# Adafruit_EZ-SFX_Mini.net
KiCad netlist of a schematic drawn in EAGLE
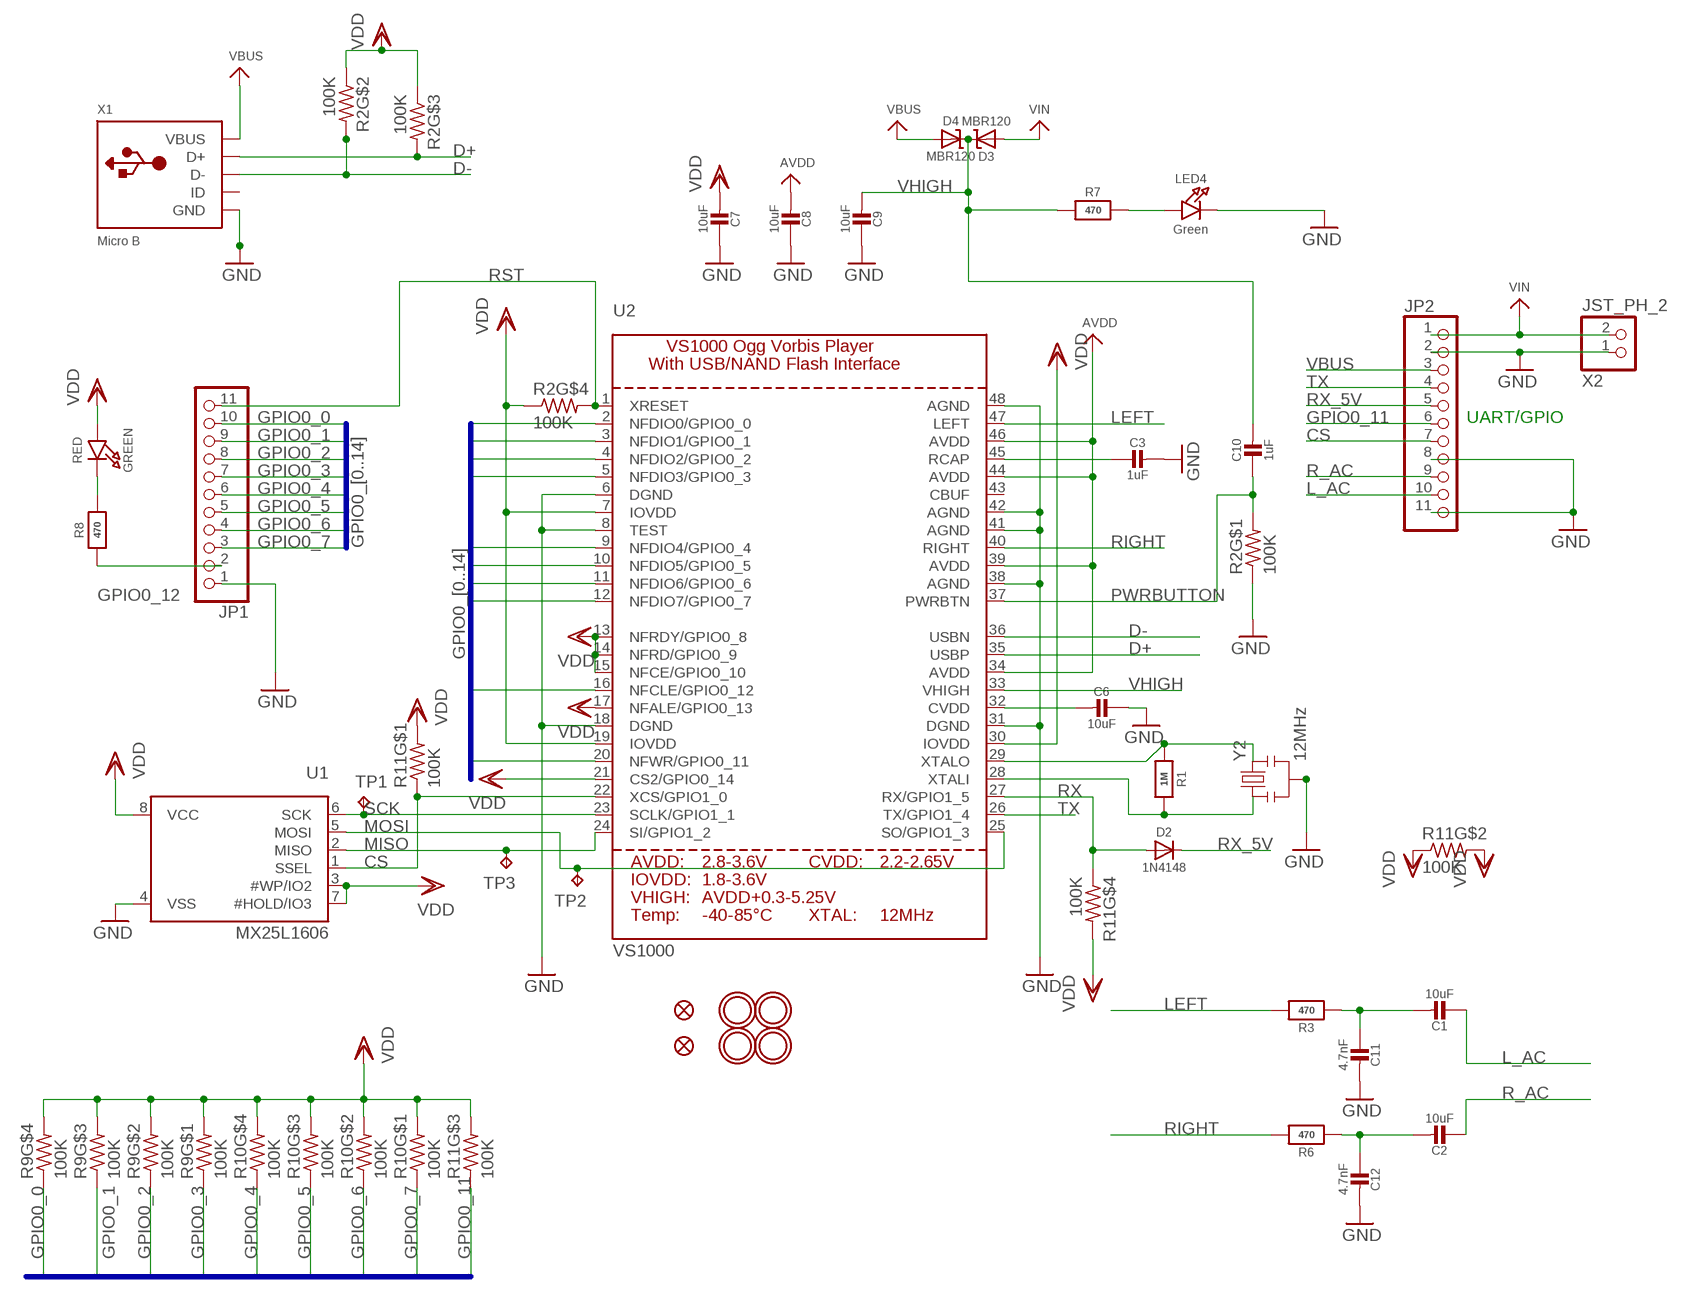
[diagram p0: schematic, sheet 1]

(export (version "E")
  (design (tool "Eeschema 10.0.6"))
  (components
    (comp (ref "C1")
      (value "10uF")
      (footprint "eagle-import:0805-NO")
      (libsource (lib "eagle-import") (part "CAP_CERAMIC0805-NOOUTLINE"))
    )
    (comp (ref "C2")
      (value "10uF")
      (footprint "eagle-import:0805-NO")
      (libsource (lib "eagle-import") (part "CAP_CERAMIC0805-NOOUTLINE"))
    )
    (comp (ref "C3")
      (value "1uF")
      (footprint "eagle-import:0805-NO")
      (libsource (lib "eagle-import") (part "CAP_CERAMIC0805-NOOUTLINE"))
    )
    (comp (ref "C6")
      (value "10uF")
      (footprint "eagle-import:0805_10MGAP")
      (libsource (lib "eagle-import") (part "CAP_CERAMIC0805_10MGAP"))
    )
    (comp (ref "C7")
      (value "10uF")
      (footprint "eagle-import:0805_10MGAP")
      (libsource (lib "eagle-import") (part "CAP_CERAMIC0805_10MGAP"))
    )
    (comp (ref "C8")
      (value "10uF")
      (footprint "eagle-import:0805-NO")
      (libsource (lib "eagle-import") (part "CAP_CERAMIC0805-NOOUTLINE"))
    )
    (comp (ref "C9")
      (value "10uF")
      (footprint "eagle-import:0805-NO")
      (libsource (lib "eagle-import") (part "CAP_CERAMIC0805-NOOUTLINE"))
    )
    (comp (ref "C10")
      (value "1uF")
      (footprint "eagle-import:0805-NO")
      (libsource (lib "eagle-import") (part "CAP_CERAMIC0805-NOOUTLINE"))
    )
    (comp (ref "C11")
      (value "4.7nF")
      (footprint "eagle-import:0805-NO")
      (libsource (lib "eagle-import") (part "CAP_CERAMIC0805-NOOUTLINE"))
    )
    (comp (ref "C12")
      (value "4.7nF")
      (footprint "eagle-import:0805-NO")
      (libsource (lib "eagle-import") (part "CAP_CERAMIC0805-NOOUTLINE"))
    )
    (comp (ref "D2")
      (value "1N4148")
      (footprint "eagle-import:SOD-323")
      (libsource (lib "eagle-import") (part "DIODESOD-323"))
    )
    (comp (ref "D3")
      (value "MBR120")
      (footprint "eagle-import:SOD-123")
      (libsource (lib "eagle-import") (part "DIODE-SCHOTTKYSOD-123"))
    )
    (comp (ref "D4")
      (value "MBR120")
      (footprint "eagle-import:SOD-123")
      (libsource (lib "eagle-import") (part "DIODE-SCHOTTKYSOD-123"))
    )
    (comp (ref "FID1")
      (value "FIDUCIAL\"\"")
      (footprint "eagle-import:FIDUCIAL_1MM")
      (libsource (lib "eagle-import") (part "FIDUCIAL{dblquote}{dblquote}"))
    )
    (comp (ref "FID2")
      (value "FIDUCIAL\"\"")
      (footprint "eagle-import:FIDUCIAL_1MM")
      (libsource (lib "eagle-import") (part "FIDUCIAL{dblquote}{dblquote}"))
    )
    (comp (ref "GREEN")
      (value "RED")
      (footprint "eagle-import:CHIPLED_0805_NOOUTLINE")
      (libsource (lib "eagle-import") (part "LED0805_NOOUTLINE"))
    )
    (comp (ref "JP1")
      (value "HEADER-1X1176MIL")
      (footprint "eagle-import:1X11_ROUND_76")
      (libsource (lib "eagle-import") (part "HEADER-1X1176MIL"))
    )
    (comp (ref "JP2")
      (value "HEADER-1X1176MIL")
      (footprint "eagle-import:1X11_ROUND_76")
      (libsource (lib "eagle-import") (part "HEADER-1X1176MIL"))
    )
    (comp (ref "LED4")
      (value "Green")
      (footprint "eagle-import:CHIPLED_0805_NOOUTLINE")
      (libsource (lib "eagle-import") (part "LED0805_NOOUTLINE"))
    )
    (comp (ref "R1")
      (value "1M")
      (footprint "eagle-import:_0805MP")
      (libsource (lib "eagle-import") (part "RESISTOR_0805MP"))
    )
    (comp (ref "R2")
      (value "100K")
      (footprint "eagle-import:RESPACK_4X0603")
      (libsource (lib "eagle-import") (part "RESISTOR_4PACK_US"))
    )
    (comp (ref "R3")
      (value "470")
      (footprint "eagle-import:0805-NO")
      (libsource (lib "eagle-import") (part "RESISTOR0805_NOOUTLINE"))
    )
    (comp (ref "R6")
      (value "470")
      (footprint "eagle-import:0805-NO")
      (libsource (lib "eagle-import") (part "RESISTOR0805_NOOUTLINE"))
    )
    (comp (ref "R7")
      (value "470")
      (footprint "eagle-import:0805-NO")
      (libsource (lib "eagle-import") (part "RESISTOR0805_NOOUTLINE"))
    )
    (comp (ref "R8")
      (value "470")
      (footprint "eagle-import:0805-NO")
      (libsource (lib "eagle-import") (part "RESISTOR0805_NOOUTLINE"))
    )
    (comp (ref "R9")
      (value "100K")
      (footprint "eagle-import:RESPACK_4X0603")
      (libsource (lib "eagle-import") (part "RESISTOR_4PACK_US"))
    )
    (comp (ref "R10")
      (value "100K")
      (footprint "eagle-import:RESPACK_4X0603")
      (libsource (lib "eagle-import") (part "RESISTOR_4PACK_US"))
    )
    (comp (ref "R11")
      (value "100K")
      (footprint "eagle-import:RESPACK_4X0603")
      (libsource (lib "eagle-import") (part "RESISTOR_4PACK_US"))
    )
    (comp (ref "TP1")
      (value "TPB1,27")
      (footprint "eagle-import:B1,27")
      (libsource (lib "eagle-import") (part "TPB1,27"))
    )
    (comp (ref "TP2")
      (value "TPB1,27")
      (footprint "eagle-import:B1,27")
      (libsource (lib "eagle-import") (part "TPB1,27"))
    )
    (comp (ref "TP3")
      (value "TPB1,27")
      (footprint "eagle-import:B1,27")
      (libsource (lib "eagle-import") (part "TPB1,27"))
    )
    (comp (ref "U$5")
      (value "MOUNTINGHOLE2.5")
      (footprint "eagle-import:MOUNTINGHOLE_2.5_PLATED")
      (libsource (lib "eagle-import") (part "MOUNTINGHOLE2.5"))
    )
    (comp (ref "U$6")
      (value "MOUNTINGHOLE2.5")
      (footprint "eagle-import:MOUNTINGHOLE_2.5_PLATED")
      (libsource (lib "eagle-import") (part "MOUNTINGHOLE2.5"))
    )
    (comp (ref "U$7")
      (value "MOUNTINGHOLE2.5")
      (footprint "eagle-import:MOUNTINGHOLE_2.5_PLATED")
      (libsource (lib "eagle-import") (part "MOUNTINGHOLE2.5"))
    )
    (comp (ref "U$8")
      (value "MOUNTINGHOLE2.5")
      (footprint "eagle-import:MOUNTINGHOLE_2.5_PLATED")
      (libsource (lib "eagle-import") (part "MOUNTINGHOLE2.5"))
    )
    (comp (ref "U1")
      (value "MX25L1606")
      (footprint "eagle-import:SOIC8_208MIL")
      (libsource (lib "eagle-import") (part "SPIFLASH_SOIC8208MIL"))
    )
    (comp (ref "U2")
      (value "VS1000")
      (footprint "eagle-import:LQFP48")
      (libsource (lib "eagle-import") (part "VS1000"))
    )
    (comp (ref "X1")
      (value "Micro B")
      (footprint "eagle-import:4UCONN_20329_V2")
      (libsource (lib "eagle-import") (part "USB_MICRO_20329_V2"))
    )
    (comp (ref "X2")
      (value "JST_PH_2")
      (footprint "eagle-import:JSTPH2")
      (libsource (lib "eagle-import") (part "CON_JST_PH_2PIN"))
    )
    (comp (ref "Y2")
      (value "12MHz")
      (footprint "eagle-import:RESONATOR-SMD")
      (libsource (lib "eagle-import") (part "RESONATORSMD"))
    )
  )
  (nets
    (net (code "6") (name "/CS") (class "Default")
      (node (ref "JP2") (pin "7") (pinfunction "7_7") (pintype "passive"))
      (node (ref "R11") (pin "1") (pinfunction "1_1") (pintype "passive"))
      (node (ref "U1") (pin "1") (pinfunction "SSEL_1") (pintype "bidirectional"))
      (node (ref "U2") (pin "22") (pinfunction "XCS/GPIO1_0_22") (pintype "bidirectional"))
    )
    (net (code "7") (name "/D+") (class "Default")
      (node (ref "R2") (pin "6") (pinfunction "2_6") (pintype "passive"))
      (node (ref "U2") (pin "35") (pinfunction "USBP_35") (pintype "bidirectional"))
      (node (ref "X1") (pin "D+") (pinfunction "D+_D+") (pintype "bidirectional"))
    )
    (net (code "8") (name "/D-") (class "Default")
      (node (ref "R2") (pin "7") (pinfunction "2_7") (pintype "passive"))
      (node (ref "U2") (pin "36") (pinfunction "USBN_36") (pintype "bidirectional"))
      (node (ref "X1") (pin "D-") (pinfunction "D-_D-") (pintype "bidirectional"))
    )
    (net (code "9") (name "/GPIO0_0") (class "Default")
      (node (ref "JP1") (pin "10") (pinfunction "10_10") (pintype "passive"))
      (node (ref "R9") (pin "4") (pinfunction "1_4") (pintype "passive"))
      (node (ref "U2") (pin "2") (pinfunction "NFDIO0/GPIO0_0_2") (pintype "bidirectional"))
    )
    (net (code "10") (name "/GPIO0_1") (class "Default")
      (node (ref "JP1") (pin "9") (pinfunction "9_9") (pintype "passive"))
      (node (ref "R9") (pin "3") (pinfunction "1_3") (pintype "passive"))
      (node (ref "U2") (pin "3") (pinfunction "NFDIO1/GPIO0_1_3") (pintype "bidirectional"))
    )
    (net (code "11") (name "/GPIO0_2") (class "Default")
      (node (ref "JP1") (pin "8") (pinfunction "8_8") (pintype "passive"))
      (node (ref "R9") (pin "2") (pinfunction "1_2") (pintype "passive"))
      (node (ref "U2") (pin "4") (pinfunction "NFDIO2/GPIO0_2_4") (pintype "bidirectional"))
    )
    (net (code "12") (name "/GPIO0_3") (class "Default")
      (node (ref "JP1") (pin "7") (pinfunction "7_7") (pintype "passive"))
      (node (ref "R9") (pin "1") (pinfunction "1_1") (pintype "passive"))
      (node (ref "U2") (pin "5") (pinfunction "NFDIO3/GPIO0_3_5") (pintype "bidirectional"))
    )
    (net (code "13") (name "/GPIO0_4") (class "Default")
      (node (ref "JP1") (pin "6") (pinfunction "6_6") (pintype "passive"))
      (node (ref "R10") (pin "4") (pinfunction "1_4") (pintype "passive"))
      (node (ref "U2") (pin "9") (pinfunction "NFDIO4/GPIO0_4_9") (pintype "bidirectional"))
    )
    (net (code "14") (name "/GPIO0_5") (class "Default")
      (node (ref "JP1") (pin "5") (pinfunction "5_5") (pintype "passive"))
      (node (ref "R10") (pin "3") (pinfunction "1_3") (pintype "passive"))
      (node (ref "U2") (pin "10") (pinfunction "NFDIO5/GPIO0_5_10") (pintype "bidirectional"))
    )
    (net (code "15") (name "/GPIO0_6") (class "Default")
      (node (ref "JP1") (pin "4") (pinfunction "4_4") (pintype "passive"))
      (node (ref "R10") (pin "2") (pinfunction "1_2") (pintype "passive"))
      (node (ref "U2") (pin "11") (pinfunction "NFDIO6/GPIO0_6_11") (pintype "bidirectional"))
    )
    (net (code "16") (name "/GPIO0_7") (class "Default")
      (node (ref "JP1") (pin "3") (pinfunction "3_3") (pintype "passive"))
      (node (ref "R10") (pin "1") (pinfunction "1_1") (pintype "passive"))
      (node (ref "U2") (pin "12") (pinfunction "NFDIO7/GPIO0_7_12") (pintype "bidirectional"))
    )
    (net (code "17") (name "/GPIO0_11") (class "Default")
      (node (ref "JP2") (pin "6") (pinfunction "6_6") (pintype "passive"))
      (node (ref "R11") (pin "3") (pinfunction "1_3") (pintype "passive"))
      (node (ref "U2") (pin "20") (pinfunction "NFWR/GPIO0_11_20") (pintype "bidirectional"))
    )
    (net (code "18") (name "/GPIO0_12") (class "Default")
      (node (ref "JP1") (pin "2") (pinfunction "2_2") (pintype "passive"))
      (node (ref "R8") (pin "2") (pinfunction "2_2") (pintype "passive"))
      (node (ref "U2") (pin "16") (pinfunction "NFCLE/GPIO0_12_16") (pintype "bidirectional"))
    )
    (net (code "20") (name "/LEFT") (class "Default")
      (node (ref "R3") (pin "1") (pinfunction "1_1") (pintype "passive"))
      (node (ref "U2") (pin "47") (pinfunction "LEFT_47") (pintype "bidirectional"))
    )
    (net (code "21") (name "/L_AC") (class "Default")
      (node (ref "C1") (pin "1") (pinfunction "1_1") (pintype "passive"))
      (node (ref "JP2") (pin "10") (pinfunction "10_10") (pintype "passive"))
    )
    (net (code "22") (name "/MISO") (class "Default")
      (node (ref "TP3") (pin "TP") (pinfunction "TP_TP") (pintype "input"))
      (node (ref "U1") (pin "2") (pinfunction "MISO_2") (pintype "bidirectional"))
      (node (ref "U2") (pin "24") (pinfunction "SI/GPIO1_2_24") (pintype "bidirectional"))
    )
    (net (code "23") (name "/MOSI") (class "Default")
      (node (ref "TP2") (pin "TP") (pinfunction "TP_TP") (pintype "input"))
      (node (ref "U1") (pin "5") (pinfunction "MOSI_5") (pintype "bidirectional"))
      (node (ref "U2") (pin "25") (pinfunction "SO/GPIO1_3_25") (pintype "bidirectional"))
    )
    (net (code "24") (name "/PWRBUTTON") (class "Default")
      (node (ref "C10") (pin "1") (pinfunction "1_1") (pintype "passive"))
      (node (ref "R2") (pin "8") (pinfunction "2_8") (pintype "passive"))
      (node (ref "U2") (pin "37") (pinfunction "PWRBTN_37") (pintype "bidirectional"))
    )
    (net (code "25") (name "/RIGHT") (class "Default")
      (node (ref "R6") (pin "1") (pinfunction "1_1") (pintype "passive"))
      (node (ref "U2") (pin "40") (pinfunction "RIGHT_40") (pintype "bidirectional"))
    )
    (net (code "26") (name "/RST") (class "Default")
      (node (ref "JP1") (pin "11") (pinfunction "11_11") (pintype "passive"))
      (node (ref "R2") (pin "5") (pinfunction "2_5") (pintype "passive"))
      (node (ref "U2") (pin "1") (pinfunction "XRESET_1") (pintype "bidirectional"))
    )
    (net (code "27") (name "/RX") (class "Default")
      (node (ref "D2") (pin "A") (pinfunction "A_A") (pintype "passive"))
      (node (ref "R11") (pin "4") (pinfunction "1_4") (pintype "passive"))
      (node (ref "U2") (pin "27") (pinfunction "RX/GPIO1_5_27") (pintype "bidirectional"))
    )
    (net (code "28") (name "/RX_5V") (class "Default")
      (node (ref "D2") (pin "C") (pinfunction "C_C") (pintype "passive"))
      (node (ref "JP2") (pin "5") (pinfunction "5_5") (pintype "passive"))
    )
    (net (code "29") (name "/R_AC") (class "Default")
      (node (ref "C2") (pin "1") (pinfunction "1_1") (pintype "passive"))
      (node (ref "JP2") (pin "9") (pinfunction "9_9") (pintype "passive"))
    )
    (net (code "30") (name "/SCK") (class "Default")
      (node (ref "TP1") (pin "TP") (pinfunction "TP_TP") (pintype "input"))
      (node (ref "U1") (pin "6") (pinfunction "SCK_6") (pintype "bidirectional"))
      (node (ref "U2") (pin "23") (pinfunction "SCLK/GPIO1_1_23") (pintype "bidirectional"))
    )
    (net (code "31") (name "/TX") (class "Default")
      (node (ref "JP2") (pin "4") (pinfunction "4_4") (pintype "passive"))
      (node (ref "U2") (pin "26") (pinfunction "TX/GPIO1_4_26") (pintype "bidirectional"))
    )
    (net (code "32") (name "/VHIGH") (class "Default")
      (node (ref "C10") (pin "2") (pinfunction "2_2") (pintype "passive"))
      (node (ref "C9") (pin "2") (pinfunction "2_2") (pintype "passive"))
      (node (ref "D3") (pin "C") (pinfunction "C_C") (pintype "passive"))
      (node (ref "D4") (pin "C") (pinfunction "C_C") (pintype "passive"))
      (node (ref "R7") (pin "2") (pinfunction "2_2") (pintype "passive"))
      (node (ref "U2") (pin "33") (pinfunction "VHIGH_33") (pintype "power_in"))
    )
    (net (code "33") (name "AVDD") (class "Default")
      (node (ref "C8") (pin "2") (pinfunction "2_2") (pintype "passive"))
      (node (ref "U2") (pin "34") (pinfunction "AVDD_34") (pintype "power_in"))
      (node (ref "U2") (pin "39") (pinfunction "AVDD_39") (pintype "power_in"))
      (node (ref "U2") (pin "44") (pinfunction "AVDD_44") (pintype "power_in"))
      (node (ref "U2") (pin "46") (pinfunction "AVDD_46") (pintype "power_in"))
    )
    (net (code "34") (name "GND") (class "Default")
      (node (ref "C11") (pin "2") (pinfunction "2_2") (pintype "passive"))
      (node (ref "C12") (pin "2") (pinfunction "2_2") (pintype "passive"))
      (node (ref "C3") (pin "2") (pinfunction "2_2") (pintype "passive"))
      (node (ref "C6") (pin "1") (pinfunction "1_1") (pintype "passive"))
      (node (ref "C7") (pin "1") (pinfunction "1_1") (pintype "passive"))
      (node (ref "C8") (pin "1") (pinfunction "1_1") (pintype "passive"))
      (node (ref "C9") (pin "1") (pinfunction "1_1") (pintype "passive"))
      (node (ref "JP1") (pin "1") (pinfunction "1_1") (pintype "passive"))
      (node (ref "JP2") (pin "11") (pinfunction "11_11") (pintype "passive"))
      (node (ref "JP2") (pin "2") (pinfunction "2_2") (pintype "passive"))
      (node (ref "JP2") (pin "8") (pinfunction "8_8") (pintype "passive"))
      (node (ref "LED4") (pin "C") (pinfunction "C_C") (pintype "passive"))
      (node (ref "R2") (pin "1") (pinfunction "1_1") (pintype "passive"))
      (node (ref "U1") (pin "4") (pinfunction "VSS_4") (pintype "bidirectional"))
      (node (ref "U2") (pin "18") (pinfunction "DGND_18") (pintype "power_in"))
      (node (ref "U2") (pin "31") (pinfunction "DGND_31") (pintype "power_in"))
      (node (ref "U2") (pin "38") (pinfunction "AGND_38") (pintype "power_in"))
      (node (ref "U2") (pin "41") (pinfunction "AGND_41") (pintype "power_in"))
      (node (ref "U2") (pin "42") (pinfunction "AGND_42") (pintype "power_in"))
      (node (ref "U2") (pin "48") (pinfunction "AGND_48") (pintype "power_in"))
      (node (ref "U2") (pin "6") (pinfunction "DGND_6") (pintype "power_in"))
      (node (ref "U2") (pin "8") (pinfunction "TEST_8") (pintype "bidirectional"))
      (node (ref "X1") (pin "BASE@1") (pinfunction "GND_BASE@1") (pintype "power_in"))
      (node (ref "X1") (pin "BASE@2") (pinfunction "GND_BASE@2") (pintype "power_in"))
      (node (ref "X1") (pin "GND") (pinfunction "GND_GND") (pintype "power_in"))
      (node (ref "X1") (pin "SPRT@1") (pinfunction "GND_SPRT@1") (pintype "power_in"))
      (node (ref "X1") (pin "SPRT@2") (pinfunction "GND_SPRT@2") (pintype "power_in"))
      (node (ref "X1") (pin "SPRT@3") (pinfunction "GND_SPRT@3") (pintype "power_in"))
      (node (ref "X1") (pin "SPRT@4") (pinfunction "GND_SPRT@4") (pintype "power_in"))
      (node (ref "X2") (pin "1") (pinfunction "1_1") (pintype "passive"))
      (node (ref "Y2") (pin "2") (pinfunction "2_2") (pintype "passive"))
    )
    (net (code "35") (name "Net-(C1-Pad2)") (class "Default")
      (node (ref "C1") (pin "2") (pinfunction "2_2") (pintype "passive"))
      (node (ref "C11") (pin "1") (pinfunction "1_1") (pintype "passive"))
      (node (ref "R3") (pin "2") (pinfunction "2_2") (pintype "passive"))
    )
    (net (code "36") (name "Net-(C12-Pad1)") (class "Default")
      (node (ref "C12") (pin "1") (pinfunction "1_1") (pintype "passive"))
      (node (ref "C2") (pin "2") (pinfunction "2_2") (pintype "passive"))
      (node (ref "R6") (pin "2") (pinfunction "2_2") (pintype "passive"))
    )
    (net (code "37") (name "Net-(GREEN-PadC)") (class "Default")
      (node (ref "GREEN") (pin "C") (pinfunction "C_C") (pintype "passive"))
      (node (ref "R8") (pin "1") (pinfunction "1_1") (pintype "passive"))
    )
    (net (code "38") (name "Net-(LED4-PadA)") (class "Default")
      (node (ref "LED4") (pin "A") (pinfunction "A_A") (pintype "passive"))
      (node (ref "R7") (pin "1") (pinfunction "1_1") (pintype "passive"))
    )
    (net (code "39") (name "Net-(U2-CVDD)") (class "Default")
      (node (ref "C6") (pin "2") (pinfunction "2_2") (pintype "passive"))
      (node (ref "U2") (pin "32") (pinfunction "CVDD_32") (pintype "power_in"))
    )
    (net (code "40") (name "Net-(U2-RCAP)") (class "Default")
      (node (ref "C3") (pin "1") (pinfunction "1_1") (pintype "passive"))
      (node (ref "U2") (pin "45") (pinfunction "RCAP_45") (pintype "bidirectional"))
    )
    (net (code "41") (name "Net-(U2-XTALI)") (class "Default")
      (node (ref "R1") (pin "1") (pinfunction "1_1") (pintype "passive"))
      (node (ref "U2") (pin "28") (pinfunction "XTALI_28") (pintype "bidirectional"))
      (node (ref "Y2") (pin "1") (pinfunction "1_1") (pintype "passive"))
    )
    (net (code "42") (name "Net-(U2-XTALO)") (class "Default")
      (node (ref "R1") (pin "2") (pinfunction "2_2") (pintype "passive"))
      (node (ref "U2") (pin "29") (pinfunction "XTALO_29") (pintype "bidirectional"))
      (node (ref "Y2") (pin "3") (pinfunction "3_3") (pintype "passive"))
    )
    (net (code "43") (name "VBUS") (class "Default")
      (node (ref "D4") (pin "A") (pinfunction "A_A") (pintype "passive"))
      (node (ref "JP2") (pin "3") (pinfunction "3_3") (pintype "passive"))
      (node (ref "X1") (pin "VBUS") (pinfunction "VBUS_VBUS") (pintype "power_in"))
    )
    (net (code "44") (name "VDD") (class "Default")
      (node (ref "C7") (pin "2") (pinfunction "2_2") (pintype "passive"))
      (node (ref "GREEN") (pin "A") (pinfunction "A_A") (pintype "passive"))
      (node (ref "R10") (pin "5") (pinfunction "2_5") (pintype "passive"))
      (node (ref "R10") (pin "6") (pinfunction "2_6") (pintype "passive"))
      (node (ref "R10") (pin "7") (pinfunction "2_7") (pintype "passive"))
      (node (ref "R10") (pin "8") (pinfunction "2_8") (pintype "passive"))
      (node (ref "R11") (pin "2") (pinfunction "1_2") (pintype "passive"))
      (node (ref "R11") (pin "5") (pinfunction "2_5") (pintype "passive"))
      (node (ref "R11") (pin "6") (pinfunction "2_6") (pintype "passive"))
      (node (ref "R11") (pin "7") (pinfunction "2_7") (pintype "passive"))
      (node (ref "R11") (pin "8") (pinfunction "2_8") (pintype "passive"))
      (node (ref "R2") (pin "2") (pinfunction "1_2") (pintype "passive"))
      (node (ref "R2") (pin "3") (pinfunction "1_3") (pintype "passive"))
      (node (ref "R2") (pin "4") (pinfunction "1_4") (pintype "passive"))
      (node (ref "R9") (pin "5") (pinfunction "2_5") (pintype "passive"))
      (node (ref "R9") (pin "6") (pinfunction "2_6") (pintype "passive"))
      (node (ref "R9") (pin "7") (pinfunction "2_7") (pintype "passive"))
      (node (ref "R9") (pin "8") (pinfunction "2_8") (pintype "passive"))
      (node (ref "U1") (pin "3") (pinfunction "#WP/IO2_3") (pintype "bidirectional"))
      (node (ref "U1") (pin "7") (pinfunction "#HOLD/IO3_7") (pintype "bidirectional"))
      (node (ref "U1") (pin "8") (pinfunction "VCC_8") (pintype "bidirectional"))
      (node (ref "U2") (pin "13") (pinfunction "NFRDY/GPIO0_8_13") (pintype "bidirectional"))
      (node (ref "U2") (pin "14") (pinfunction "NFRD/GPIO0_9_14") (pintype "bidirectional"))
      (node (ref "U2") (pin "15") (pinfunction "NFCE/GPIO0_10_15") (pintype "bidirectional"))
      (node (ref "U2") (pin "17") (pinfunction "NFALE/GPIO0_13_17") (pintype "bidirectional"))
      (node (ref "U2") (pin "19") (pinfunction "IOVDD_19") (pintype "power_in"))
      (node (ref "U2") (pin "21") (pinfunction "CS2/GPIO0_14_21") (pintype "bidirectional"))
      (node (ref "U2") (pin "30") (pinfunction "IOVDD_30") (pintype "power_in"))
      (node (ref "U2") (pin "7") (pinfunction "IOVDD_7") (pintype "power_in"))
    )
    (net (code "45") (name "VIN") (class "Default")
      (node (ref "D3") (pin "A") (pinfunction "A_A") (pintype "passive"))
      (node (ref "JP2") (pin "1") (pinfunction "1_1") (pintype "passive"))
      (node (ref "X2") (pin "2") (pinfunction "2_2") (pintype "passive"))
    )
    (net (code "46") (name "unconnected-(U2-CBUF-Pad43)") (class "Default")
      (node (ref "U2") (pin "43") (pinfunction "CBUF_43") (pintype "bidirectional"))
    )
    (net (code "47") (name "unconnected-(X1-PadID)") (class "Default")
      (node (ref "X1") (pin "ID") (pinfunction "ID_ID") (pintype "bidirectional"))
    )
  )
)
